# sensors.net
KiCad netlist of a schematic drawn in Altium Designer
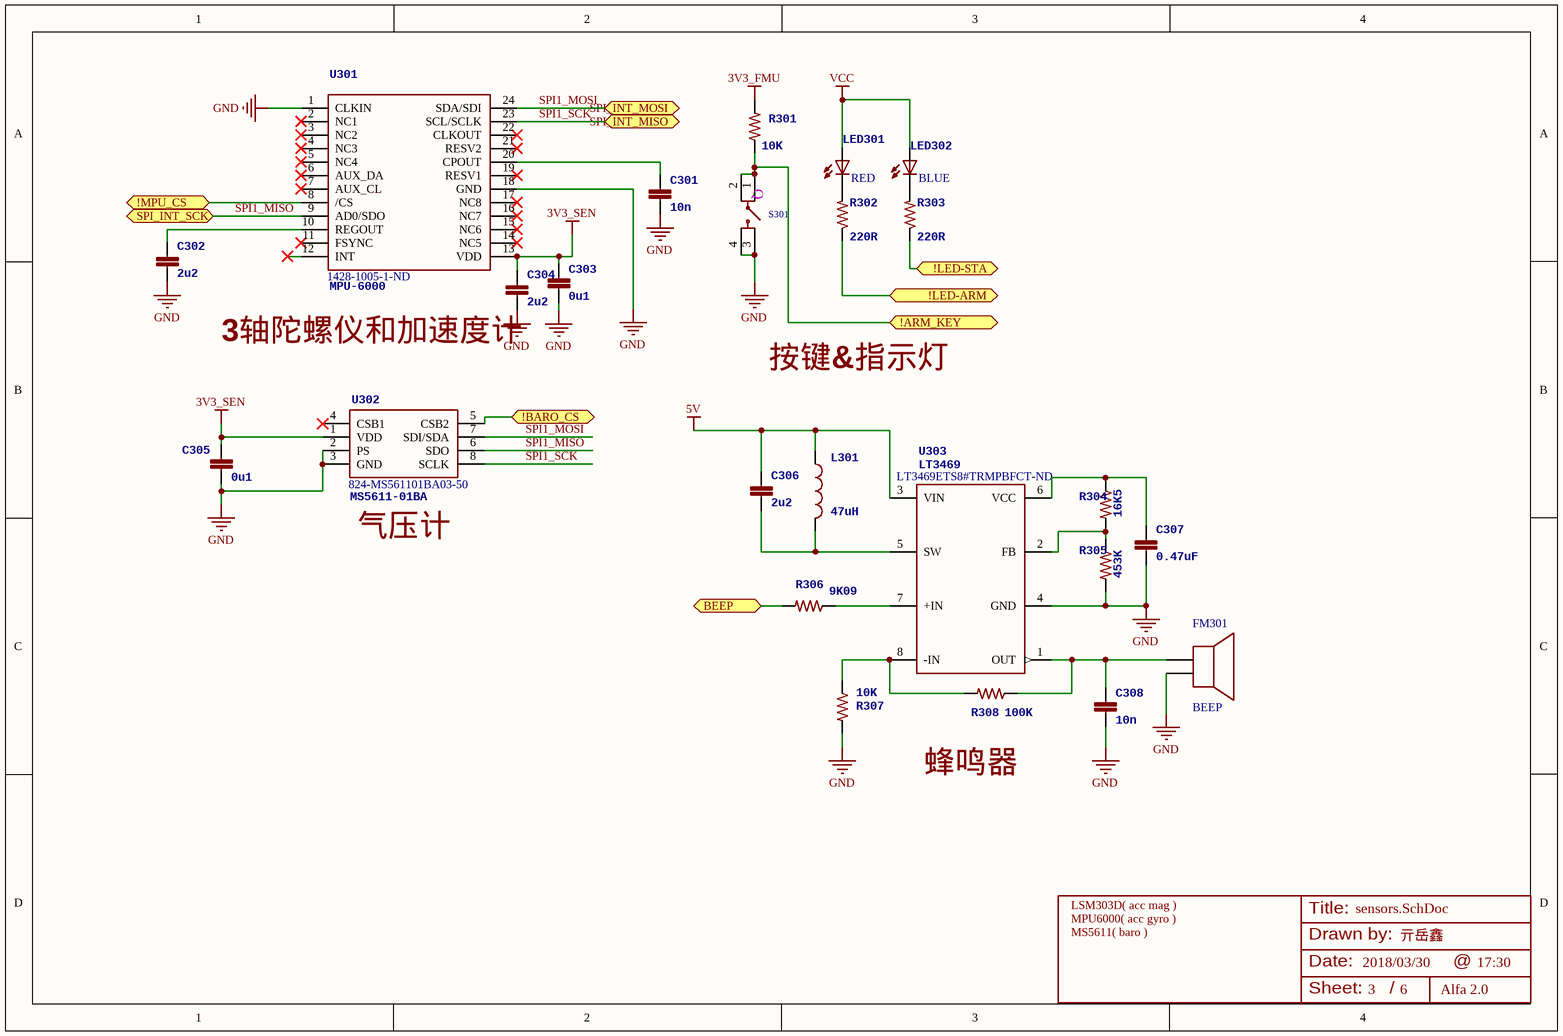
[diagram p0: sensors.SchDoc]

(export (version "E")
  (design (tool "Eeschema 10.0.6"))
  (components
    (comp (ref "C301")
      (value "10n")
      (footprint "0603-CAP")
      (description "Capacitor, 10nF, 50V")
      (fields (field (name "PARTNO") "CC0402ZRY5V7BB104") (field (name "3DR_PARTNO") "ECM0700"))
      (libsource (lib "Q's无源元件类") (part "CAP0603-10nF"))
    )
    (comp (ref "C302")
      (value "2u2")
      (footprint "0603-CAP")
      (description "Capacitor, 2.2uF, 16V, 10%, X6S, 0603, Ceramic")
      (fields (field (name "PARTNO") "C1608X6S1C225K080AC") (field (name "3DR_PARTNO") "ECM0619"))
      (libsource (lib "Q's无源元件类") (part "CAP0603-2.2uF"))
    )
    (comp (ref "C303")
      (value "0u1")
      (footprint "0603-CAP")
      (description "Capacitor, 0.1uF, 16V, Y5V, 0402, Ceramic")
      (fields (field (name "PARTNO") "CC0402ZRY5V7BB104") (field (name "3DR_PARTNO") "ECM0700"))
      (libsource (lib "") (part "CAP0603-0.1uF_1"))
    )
    (comp (ref "C304")
      (value "2u2")
      (footprint "0603-CAP")
      (description "Capacitor, 2.2uF, 16V, 10%, X6S, 0603, Ceramic")
      (fields (field (name "PARTNO") "C1608X6S1C225K080AC") (field (name "3DR_PARTNO") "ECM0619"))
      (libsource (lib "Q's无源元件类") (part "CAP0603-2.2uF"))
    )
    (comp (ref "C305")
      (value "0u1")
      (footprint "0603-CAP")
      (description "Capacitor, 0.1uF, 16V, Y5V, 0402, Ceramic")
      (fields (field (name "PARTNO") "CC0402ZRY5V7BB104") (field (name "3DR_PARTNO") "ECM0700"))
      (libsource (lib "Q's无源元件类") (part "CAP0603-0.1uF"))
    )
    (comp (ref "C306")
      (value "2u2")
      (footprint "0603-CAP")
      (description "Capacitor, 2.2uF, 16V, 10%, X6S, 0603, Ceramic")
      (fields (field (name "PARTNO") "C1608X6S1C225K080AC") (field (name "3DR_PARTNO") "ECM0619"))
      (libsource (lib "Q's无源元件类") (part "CAP0603-2.2uF"))
    )
    (comp (ref "C307")
      (value "0.47uF")
      (footprint "0603-CAP")
      (description "Capacitor, 0.47uF, 16V, 10%, X6S, 0603, Ceramic")
      (fields (field (name "3DR_PARTNO") "ECM0619"))
      (libsource (lib "Q's无源元件类") (part "CAP0603-0.47uF"))
    )
    (comp (ref "C308")
      (value "10n")
      (footprint "0603-CAP")
      (description "Capacitor, 10nF, 50V")
      (fields (field (name "PARTNO") "CC0402ZRY5V7BB104") (field (name "3DR_PARTNO") "ECM0700"))
      (libsource (lib "Q's无源元件类") (part "CAP0603-10nF"))
    )
    (comp (ref "FM301")
      (value "BEEP")
      (footprint "BEEP-12mm")
      (description "蜂鸣器")
      (libsource (lib "Q's无源元件类") (part "BEEP"))
    )
    (comp (ref "L301")
      (value "47uH")
      (footprint "1210 - IND")
      (description "贴片功率电感，绕线工字电感")
      (fields (field (name "PARTNO") "LQH32CN470, 1.3Ω") (field (name "3DR_PARTNO") "ECM0814"))
      (libsource (lib "Q's无源元件类") (part "INDUCTOR-1210"))
    )
    (comp (ref "LED301")
      (value "APT1608SECK")
      (footprint "0603-LED")
      (description "2.2v, LED RED CLEAR 0603 SMD")
      (fields (field (name "3DR_PARTNO") "ECM0515") (field (name "COLOR") "RED"))
      (libsource (lib "Q's无源元件类") (part "LED0603-RED"))
    )
    (comp (ref "LED302")
      (value "APT1608QBC/G")
      (footprint "0603-LED")
      (description "3.3v, LED BLUE CLEAR 0603 SMD")
      (fields (field (name "3DR_PARTNO") "ECM0515") (field (name "COLOR") "BLUE"))
      (libsource (lib "Q's无源元件类") (part "LED0603-BLUE"))
    )
    (comp (ref "R301")
      (value "10K")
      (footprint "0603-RES")
      (description "RES 10K OHM 1/10W 5% 0603")
      (libsource (lib "Q's无源元件类") (part "RES0603-10K"))
    )
    (comp (ref "R302")
      (value "220R")
      (footprint "0603-RES")
      (description "RES 220R OHM 1/10W 5% 0603")
      (libsource (lib "Q's无源元件类") (part "RES0603-220R"))
    )
    (comp (ref "R303")
      (value "220R")
      (footprint "0603-RES")
      (description "RES 220R OHM 1/10W 5% 0603")
      (libsource (lib "Q's无源元件类") (part "RES0603-220R"))
    )
    (comp (ref "R304")
      (value "16K5")
      (footprint "0603-RES")
      (description "RES 16K5 OHM 1/10W 5% 0603")
      (libsource (lib "Q's无源元件类") (part "RES0603-16K5"))
    )
    (comp (ref "R305")
      (value "453K")
      (footprint "0603-RES")
      (description "RES 453K OHM 1/10W 5% 0603")
      (libsource (lib "Q's无源元件类") (part "RES0603-453K"))
    )
    (comp (ref "R306")
      (value "9K09")
      (footprint "0603-RES")
      (description "RES 9K09 OHM 1/10W 5% 0603")
      (libsource (lib "Q's无源元件类") (part "RES0603-9K09"))
    )
    (comp (ref "R307")
      (value "10K")
      (footprint "0603-RES")
      (description "RES 10K OHM 1/10W 5% 0603")
      (libsource (lib "Q's无源元件类") (part "RES0603-10K"))
    )
    (comp (ref "R308")
      (value "100K")
      (footprint "0603-RES")
      (description "RES 100K OHM 1/10W 5% 0603")
      (libsource (lib "Q's无源元件类") (part "RES0603-100K"))
    )
    (comp (ref "S301")
      (value "SWITCH")
      (footprint "SW_6*6")
      (description "6*6*4.3 微动轻触开关贴片")
      (libsource (lib "Q's无源元件类") (part "SWITCH"))
    )
    (comp (ref "U301")
      (value "MPU-6000")
      (footprint "QFN-24")
      (description "GYRO/ACCELEROMETER 6AXIS 24QFN")
      (fields (field (name "3DR_PARTNO") "ECM0834") (field (name "SUPPLIER PART NUMBER 1") "1428-1005-1-ND"))
      (libsource (lib "Q's有源芯片类") (part "MPU-6000"))
    )
    (comp (ref "U302")
      (value "MS5611-01BA")
      (footprint "MS5611-01BA")
      (description "Board Mount Pressure Sensors")
      (fields
        (field (name "3DR_PARTNO") "ECM0835")
        (field (name "SUPPLIER PART NUMBER 1") "824-MS561101BA03-50")
      )
      (libsource (lib "Q's有源芯片类") (part "MS5611-01BA"))
    )
    (comp (ref "U303")
      (value "LT3469")
      (footprint "SOT23-8")
      (description "IC AMP DVR W/REG 1.3MHZ TSOT23-8")
      (fields
        (field (name "3DR_PARTNO") "ECM0829")
        (field (name "SUPPLIER PART NUMBER 1") "LT3469ETS8#TRMPBFCT-ND")
      )
      (libsource (lib "Q's有源芯片类") (part "LT3469"))
    )
  )
  (nets
    (net (code "1") (name "/!ARM_KEY") (class "Default")
      (node (ref "R301") (pin "1") (pinfunction "1_1") (pintype "passive"))
      (node (ref "S301") (pin "1") (pinfunction "1_1") (pintype "passive"))
      (node (ref "S301") (pin "2") (pinfunction "2_2") (pintype "passive"))
    )
    (net (code "2") (name "/!BARO_CS") (class "Default")
      (node (ref "U302") (pin "5") (pinfunction "CSB2_5") (pintype "passive"))
    )
    (net (code "3") (name "/!LED-ARM") (class "Default")
      (node (ref "R302") (pin "1") (pinfunction "1_1") (pintype "passive"))
    )
    (net (code "4") (name "/!LED-STA") (class "Default")
      (node (ref "R303") (pin "1") (pinfunction "1_1") (pintype "passive"))
    )
    (net (code "5") (name "/!MPU_CS") (class "Default")
      (node (ref "U301") (pin "8") (pinfunction "/CS_8") (pintype "passive"))
    )
    (net (code "6") (name "/BEEP") (class "Default")
      (node (ref "R306") (pin "2") (pinfunction "2_2") (pintype "passive"))
    )
    (net (code "7") (name "/SPI1_MISO") (class "Default")
      (node (ref "U301") (pin "9") (pinfunction "AD0/SDO_9") (pintype "passive"))
      (node (ref "U302") (pin "6") (pinfunction "SDO_6") (pintype "passive"))
    )
    (net (code "8") (name "/SPI1_MOSI") (class "Default")
      (node (ref "U301") (pin "24") (pinfunction "SDA/SDI_24") (pintype "passive"))
      (node (ref "U302") (pin "7") (pinfunction "SDI/SDA_7") (pintype "passive"))
    )
    (net (code "9") (name "/SPI1_SCK") (class "Default")
      (node (ref "U301") (pin "23") (pinfunction "SCL/SCLK_23") (pintype "passive"))
      (node (ref "U302") (pin "8") (pinfunction "SCLK_8") (pintype "passive"))
    )
    (net (code "10") (name "3V3_FMU") (class "Default")
      (node (ref "R301") (pin "2") (pinfunction "2_2") (pintype "passive"))
    )
    (net (code "11") (name "3V3_SEN") (class "Default")
      (node (ref "C303") (pin "P$1") (pinfunction "1_P$1") (pintype "passive"))
      (node (ref "C304") (pin "P$1") (pinfunction "1_P$1") (pintype "passive"))
      (node (ref "C305") (pin "P$1") (pinfunction "1_P$1") (pintype "passive"))
      (node (ref "U301") (pin "13") (pinfunction "VDD_13") (pintype "passive"))
      (node (ref "U302") (pin "1") (pinfunction "VDD_1") (pintype "passive"))
    )
    (net (code "12") (name "5V") (class "Default")
      (node (ref "C306") (pin "P$1") (pinfunction "1_P$1") (pintype "passive"))
      (node (ref "L301") (pin "1") (pinfunction "1_1") (pintype "passive"))
      (node (ref "U303") (pin "3") (pinfunction "VIN_3") (pintype "passive"))
    )
    (net (code "13") (name "GND") (class "Default")
      (node (ref "C301") (pin "P$2") (pinfunction "2_P$2") (pintype "passive"))
      (node (ref "C302") (pin "P$2") (pinfunction "2_P$2") (pintype "passive"))
      (node (ref "C303") (pin "P$2") (pinfunction "2_P$2") (pintype "passive"))
      (node (ref "C304") (pin "P$2") (pinfunction "2_P$2") (pintype "passive"))
      (node (ref "C305") (pin "P$2") (pinfunction "2_P$2") (pintype "passive"))
      (node (ref "C307") (pin "P$2") (pinfunction "2_P$2") (pintype "passive"))
      (node (ref "C308") (pin "P$2") (pinfunction "2_P$2") (pintype "passive"))
      (node (ref "FM301") (pin "2") (pinfunction "2_2") (pintype "passive"))
      (node (ref "R305") (pin "2") (pinfunction "2_2") (pintype "passive"))
      (node (ref "R307") (pin "2") (pinfunction "2_2") (pintype "passive"))
      (node (ref "S301") (pin "3") (pinfunction "3_3") (pintype "passive"))
      (node (ref "S301") (pin "4") (pinfunction "4_4") (pintype "passive"))
      (node (ref "U301") (pin "1") (pinfunction "CLKIN_1") (pintype "passive"))
      (node (ref "U301") (pin "18") (pinfunction "GND_18") (pintype "passive"))
      (node (ref "U302") (pin "2") (pinfunction "PS_2") (pintype "passive"))
      (node (ref "U302") (pin "3") (pinfunction "GND_3") (pintype "passive"))
      (node (ref "U303") (pin "4") (pinfunction "GND_4") (pintype "passive"))
    )
    (net (code "14") (name "Net-(C301-1)") (class "Default")
      (node (ref "C301") (pin "P$1") (pinfunction "1_P$1") (pintype "passive"))
      (node (ref "U301") (pin "20") (pinfunction "CPOUT_20") (pintype "passive"))
    )
    (net (code "15") (name "Net-(C302-1)") (class "Default")
      (node (ref "C302") (pin "P$1") (pinfunction "1_P$1") (pintype "passive"))
      (node (ref "U301") (pin "10") (pinfunction "REGOUT_10") (pintype "passive"))
    )
    (net (code "16") (name "Net-(C306-2)") (class "Default")
      (node (ref "C306") (pin "P$2") (pinfunction "2_P$2") (pintype "passive"))
      (node (ref "L301") (pin "2") (pinfunction "2_2") (pintype "passive"))
      (node (ref "U303") (pin "5") (pinfunction "SW_5") (pintype "passive"))
    )
    (net (code "17") (name "Net-(C307-1)") (class "Default")
      (node (ref "C307") (pin "P$1") (pinfunction "1_P$1") (pintype "passive"))
      (node (ref "R304") (pin "1") (pinfunction "1_1") (pintype "passive"))
      (node (ref "U303") (pin "6") (pinfunction "VCC_6") (pintype "passive"))
    )
    (net (code "18") (name "Net-(C308-1)") (class "Default")
      (node (ref "C308") (pin "P$1") (pinfunction "1_P$1") (pintype "passive"))
      (node (ref "FM301") (pin "1") (pinfunction "1_1") (pintype "passive"))
      (node (ref "R308") (pin "1") (pinfunction "1_1") (pintype "passive"))
      (node (ref "U303") (pin "1") (pinfunction "OUT_1") (pintype "output"))
    )
    (net (code "19") (name "Net-(LED301-PadC)") (class "Default")
      (node (ref "LED301") (pin "C") (pinfunction "C_C") (pintype "passive"))
      (node (ref "R302") (pin "2") (pinfunction "2_2") (pintype "passive"))
    )
    (net (code "20") (name "Net-(LED302-PadC)") (class "Default")
      (node (ref "LED302") (pin "C") (pinfunction "C_C") (pintype "passive"))
      (node (ref "R303") (pin "2") (pinfunction "2_2") (pintype "passive"))
    )
    (net (code "21") (name "Net-(U303-+IN)") (class "Default")
      (node (ref "R306") (pin "1") (pinfunction "1_1") (pintype "passive"))
      (node (ref "U303") (pin "7") (pinfunction "+IN_7") (pintype "passive"))
    )
    (net (code "22") (name "Net-(U303--IN)") (class "Default")
      (node (ref "R307") (pin "1") (pinfunction "1_1") (pintype "passive"))
      (node (ref "R308") (pin "2") (pinfunction "2_2") (pintype "passive"))
      (node (ref "U303") (pin "8") (pinfunction "-IN_8") (pintype "passive"))
    )
    (net (code "23") (name "Net-(U303-FB)") (class "Default")
      (node (ref "R304") (pin "2") (pinfunction "2_2") (pintype "passive"))
      (node (ref "R305") (pin "1") (pinfunction "1_1") (pintype "passive"))
      (node (ref "U303") (pin "2") (pinfunction "FB_2") (pintype "passive"))
    )
    (net (code "24") (name "VCC") (class "Default")
      (node (ref "LED301") (pin "A") (pinfunction "A_A") (pintype "passive"))
      (node (ref "LED302") (pin "A") (pinfunction "A_A") (pintype "passive"))
    )
    (net (code "25") (name "unconnected-(U301-AUX_CL-Pad7)") (class "Default")
      (node (ref "U301") (pin "7") (pinfunction "AUX_CL_7") (pintype "passive+no_connect"))
    )
    (net (code "26") (name "unconnected-(U301-AUX_DA-Pad6)") (class "Default")
      (node (ref "U301") (pin "6") (pinfunction "AUX_DA_6") (pintype "passive+no_connect"))
    )
    (net (code "27") (name "unconnected-(U301-CLKOUT-Pad22)") (class "Default")
      (node (ref "U301") (pin "22") (pinfunction "CLKOUT_22") (pintype "passive+no_connect"))
    )
    (net (code "28") (name "unconnected-(U301-FSYNC-Pad11)") (class "Default")
      (node (ref "U301") (pin "11") (pinfunction "FSYNC_11") (pintype "passive+no_connect"))
    )
    (net (code "29") (name "unconnected-(U301-INT-Pad12)") (class "Default")
      (node (ref "U301") (pin "12") (pinfunction "INT_12") (pintype "passive"))
    )
    (net (code "30") (name "unconnected-(U301-NC1-Pad2)") (class "Default")
      (node (ref "U301") (pin "2") (pinfunction "NC1_2") (pintype "passive+no_connect"))
    )
    (net (code "31") (name "unconnected-(U301-NC2-Pad3)") (class "Default")
      (node (ref "U301") (pin "3") (pinfunction "NC2_3") (pintype "passive+no_connect"))
    )
    (net (code "32") (name "unconnected-(U301-NC3-Pad4)") (class "Default")
      (node (ref "U301") (pin "4") (pinfunction "NC3_4") (pintype "passive+no_connect"))
    )
    (net (code "33") (name "unconnected-(U301-NC4-Pad5)") (class "Default")
      (node (ref "U301") (pin "5") (pinfunction "NC4_5") (pintype "passive+no_connect"))
    )
    (net (code "34") (name "unconnected-(U301-NC5-Pad14)") (class "Default")
      (node (ref "U301") (pin "14") (pinfunction "NC5_14") (pintype "passive+no_connect"))
    )
    (net (code "35") (name "unconnected-(U301-NC6-Pad15)") (class "Default")
      (node (ref "U301") (pin "15") (pinfunction "NC6_15") (pintype "passive+no_connect"))
    )
    (net (code "36") (name "unconnected-(U301-NC7-Pad16)") (class "Default")
      (node (ref "U301") (pin "16") (pinfunction "NC7_16") (pintype "passive+no_connect"))
    )
    (net (code "37") (name "unconnected-(U301-NC8-Pad17)") (class "Default")
      (node (ref "U301") (pin "17") (pinfunction "NC8_17") (pintype "passive+no_connect"))
    )
    (net (code "38") (name "unconnected-(U301-RESV1-Pad19)") (class "Default")
      (node (ref "U301") (pin "19") (pinfunction "RESV1_19") (pintype "passive+no_connect"))
    )
    (net (code "39") (name "unconnected-(U301-RESV2-Pad21)") (class "Default")
      (node (ref "U301") (pin "21") (pinfunction "RESV2_21") (pintype "passive+no_connect"))
    )
    (net (code "40") (name "unconnected-(U302-CSB1-Pad4)") (class "Default")
      (node (ref "U302") (pin "4") (pinfunction "CSB1_4") (pintype "passive+no_connect"))
    )
  )
)
